# 2.net
KiCad netlist of a schematic drawn in Altium Designer
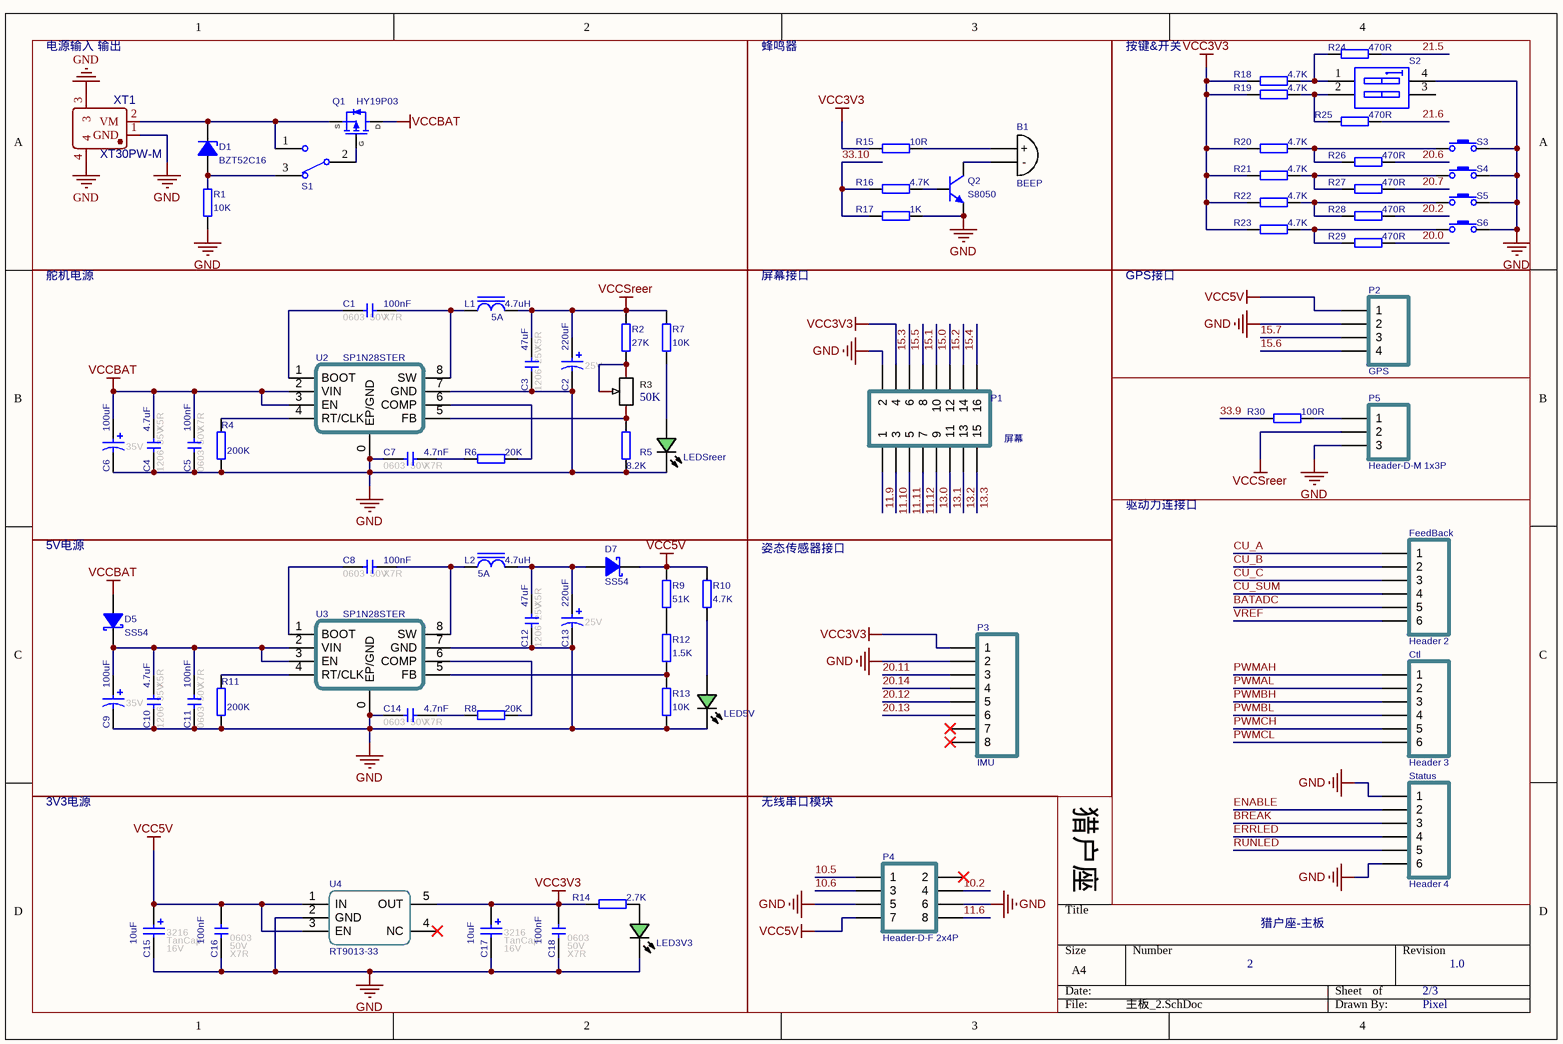
[diagram p0: 主板_2.SchDoc]

(export (version "E")
  (design (tool "Eeschema 10.0.6"))
  (components
    (comp (ref "B1")
      (value "BEEP")
      (footprint "BEEP 9x5.5mm")
      (description "蜂鸣器")
      (libsource (lib "TC264_主板_V2.6") (part "BEEP"))
    )
    (comp (ref "C1")
      (value "100nF")
      (footprint "0603")
      (description "贴片瓷片电容; MLCC; 0603(1608);")
      (fields
        (field (name "VOLTAGE") "50V")
        (field (name "TYPE") "X7R")
        (field (name "Comment") "100nF 50V X7R")
      )
      (libsource (lib "TC264_主板_V2.6") (part "100nF 0603 50V X7R"))
    )
    (comp (ref "C2")
      (value "220uF")
      (footprint "CAP-E-S 6.3")
      (description "贴片电解电容 220uF 25V 6.3x7.7")
      (fields (field (name "VOLTAGE") "25V") (field (name "Comment") "220uF 25V 铝电解"))
      (libsource (lib "TC264_主板_V2.6") (part "E-S 220uF 25V 6.3x7.7"))
    )
    (comp (ref "C3")
      (value "47uF")
      (footprint "1206")
      (description "贴片瓷片电容; MLCC; 1206(3216);")
      (fields
        (field (name "VOLTAGE") "25V")
        (field (name "TYPE") "X5R")
        (field (name "Comment") "47uF 25V X5R")
      )
      (libsource (lib "TC264_主板_V2.6") (part "47uF 1206 25V X5R"))
    )
    (comp (ref "C4")
      (value "4.7uF")
      (footprint "1206")
      (description "贴片瓷片电容; MLCC; 1206(3216);")
      (fields
        (field (name "VOLTAGE") "35V")
        (field (name "TYPE") "X5R")
        (field (name "Comment") "4.7uF 35V X5R")
      )
      (libsource (lib "TC264_主板_V2.6") (part "4.7uF 1206 35V X5R"))
    )
    (comp (ref "C5")
      (value "100nF")
      (footprint "0603")
      (description "贴片瓷片电容; MLCC; 0603(1608);")
      (fields
        (field (name "VOLTAGE") "50V")
        (field (name "TYPE") "X7R")
        (field (name "Comment") "100nF 50V X7R")
      )
      (libsource (lib "TC264_主板_V2.6") (part "100nF 0603 50V X7R"))
    )
    (comp (ref "C6")
      (value "100uF")
      (footprint "CAP-E-S 6.3")
      (description "贴片电解电容 100uF 35V 6.3x7.7")
      (fields (field (name "VOLTAGE") "35V") (field (name "Comment") "100uF 35V 铝电解"))
      (libsource (lib "TC264_主板_V2.6") (part "E-S 100uF 35V 6.3x7.7"))
    )
    (comp (ref "C7")
      (value "4.7nF")
      (footprint "0603")
      (description "贴片瓷片电容; MLCC; 0603(1608);")
      (fields
        (field (name "VOLTAGE") "50V")
        (field (name "TYPE") "X7R")
        (field (name "Comment") "4.7nF 50V X7R")
      )
      (libsource (lib "TC264_主板_V2.6") (part "4.7nF 0603 50V X7R"))
    )
    (comp (ref "C8")
      (value "100nF")
      (footprint "0603")
      (description "贴片瓷片电容; MLCC; 0603(1608);")
      (fields
        (field (name "VOLTAGE") "50V")
        (field (name "TYPE") "X7R")
        (field (name "Comment") "100nF 50V X7R")
      )
      (libsource (lib "TC264_主板_V2.6") (part "100nF 0603 50V X7R"))
    )
    (comp (ref "C9")
      (value "100uF")
      (footprint "CAP-E-S 6.3")
      (description "贴片电解电容 100uF 35V 6.3x7.7")
      (fields (field (name "VOLTAGE") "35V") (field (name "Comment") "100uF 35V 铝电解"))
      (libsource (lib "TC264_主板_V2.6") (part "E-S 100uF 35V 6.3x7.7"))
    )
    (comp (ref "C10")
      (value "4.7uF")
      (footprint "1206")
      (description "贴片瓷片电容; MLCC; 1206(3216);")
      (fields
        (field (name "VOLTAGE") "35V")
        (field (name "TYPE") "X5R")
        (field (name "Comment") "4.7uF 35V X5R")
      )
      (libsource (lib "TC264_主板_V2.6") (part "4.7uF 1206 35V X5R"))
    )
    (comp (ref "C11")
      (value "100nF")
      (footprint "0603")
      (description "贴片瓷片电容; MLCC; 0603(1608);")
      (fields
        (field (name "VOLTAGE") "50V")
        (field (name "TYPE") "X7R")
        (field (name "Comment") "100nF 50V X7R")
      )
      (libsource (lib "TC264_主板_V2.6") (part "100nF 0603 50V X7R"))
    )
    (comp (ref "C12")
      (value "47uF")
      (footprint "1206")
      (description "贴片瓷片电容; MLCC; 1206(3216);")
      (fields
        (field (name "VOLTAGE") "25V")
        (field (name "TYPE") "X5R")
        (field (name "Comment") "47uF 25V X5R")
      )
      (libsource (lib "TC264_主板_V2.6") (part "47uF 1206 25V X5R"))
    )
    (comp (ref "C13")
      (value "220uF")
      (footprint "CAP-E-S 6.3")
      (description "贴片电解电容 220uF 25V 6.3x7.7")
      (fields (field (name "VOLTAGE") "25V") (field (name "Comment") "220uF 25V 铝电解"))
      (libsource (lib "TC264_主板_V2.6") (part "E-S 220uF 25V 6.3x7.7"))
    )
    (comp (ref "C14")
      (value "4.7nF")
      (footprint "0603")
      (description "贴片瓷片电容; MLCC; 0603(1608);")
      (fields
        (field (name "VOLTAGE") "50V")
        (field (name "TYPE") "X7R")
        (field (name "Comment") "4.7nF 50V X7R")
      )
      (libsource (lib "TC264_主板_V2.6") (part "4.7nF 0603 50V X7R"))
    )
    (comp (ref "C15")
      (value "10uF")
      (footprint "3216")
      (description "贴片钽电容 10uF 3216 16V")
      (fields
        (field (name "TYPE") "TanCap")
        (field (name "VOLTAGE") "16V")
        (field (name "Comment") "10uF 16V 钽电容")
      )
      (libsource (lib "TC264_主板_V2.6") (part "T-S 10uF 3216 16V"))
    )
    (comp (ref "C16")
      (value "100nF")
      (footprint "0603")
      (description "贴片瓷片电容; MLCC; 0603(1608);")
      (fields
        (field (name "VOLTAGE") "50V")
        (field (name "TYPE") "X7R")
        (field (name "Comment") "100nF 50V X7R")
      )
      (libsource (lib "TC264_主板_V2.6") (part "100nF 0603 50V X7R"))
    )
    (comp (ref "C17")
      (value "10uF")
      (footprint "3216")
      (description "贴片钽电容 10uF 3216 16V")
      (fields
        (field (name "TYPE") "TanCap")
        (field (name "VOLTAGE") "16V")
        (field (name "Comment") "10uF 16V 钽电容")
      )
      (libsource (lib "TC264_主板_V2.6") (part "T-S 10uF 3216 16V"))
    )
    (comp (ref "C18")
      (value "100nF")
      (footprint "0603")
      (description "贴片瓷片电容; MLCC; 0603(1608);")
      (fields
        (field (name "VOLTAGE") "50V")
        (field (name "TYPE") "X7R")
        (field (name "Comment") "100nF 50V X7R")
      )
      (libsource (lib "TC264_主板_V2.6") (part "100nF 0603 50V X7R"))
    )
    (comp (ref "Ctl")
      (value "Header 3")
      (footprint "ZH1.5-6P-SH")
      (description "Header, 6-Pin")
      (fields (field (name "PUBLISHER") "Altium Limited"))
      (libsource (lib "无刷驱动-Infineon-AUIRS2181S-GTM-6S") (part "Header 6"))
    )
    (comp (ref "D1")
      (value "BZT52C16")
      (footprint "SOD-123-L")
      (description "稳压二极管 齐纳二极管  Zener Diode")
      (fields (field (name "PUBLISHER") "Altium Limited"))
      (libsource (lib "TC264_主板_V2.6") (part "Diode Zen"))
    )
    (comp (ref "D5")
      (value "SS54")
      (footprint "SMA-L[DO-214AC]")
      (description "SS54 肖特基二极管")
      (libsource (lib "TC264_主板_V2.6") (part "SS54"))
    )
    (comp (ref "D7")
      (value "SS54")
      (footprint "SMA-L[DO-214AC]")
      (description "SS54 肖特基二极管")
      (libsource (lib "TC264_主板_V2.6") (part "SS54"))
    )
    (comp (ref "FeedBack")
      (value "Header 2")
      (footprint "ZH1.5-6P-SH")
      (description "Header, 6-Pin")
      (fields (field (name "PUBLISHER") "Altium Limited"))
      (libsource (lib "无刷驱动-Infineon-AUIRS2181S-GTM-6S") (part "Header 6"))
    )
    (comp (ref "L1")
      (value "4.7uH")
      (footprint "0630 TPC 7*7*3")
      (description "功率电感")
      (fields
        (field (name "IMAX") "5A")
        (field (name "Comment") "4.7uH 5A")
        (field (name "PUBLISHER") "Altium Limited")
      )
      (libsource (lib "TC264_主板_V2.6") (part "Ind-Power"))
    )
    (comp (ref "L2")
      (value "4.7uH")
      (footprint "0630 TPC 7*7*3")
      (description "功率电感")
      (fields
        (field (name "IMAX") "5A")
        (field (name "Comment") "4.7uH 5A")
        (field (name "PUBLISHER") "Altium Limited")
      )
      (libsource (lib "TC264_主板_V2.6") (part "Ind-Power"))
    )
    (comp (ref "LED3V3")
      (value "翠绿贴片LED")
      (footprint "LEDC1608(0603)-L")
      (fields (field (name "PUBLISHER") "Altium Limited"))
      (libsource (lib "TC264_主板_V2.6") (part "LED Chip Green"))
    )
    (comp (ref "LED5V")
      (value "翠绿贴片LED")
      (footprint "LEDC1608(0603)-L")
      (fields (field (name "PUBLISHER") "Altium Limited"))
      (libsource (lib "TC264_主板_V2.6") (part "LED Chip Green"))
    )
    (comp (ref "LEDSreer")
      (value "翠绿贴片LED")
      (footprint "LEDC1608(0603)-L")
      (fields (field (name "PUBLISHER") "Altium Limited"))
      (libsource (lib "TC264_主板_V2.6") (part "LED Chip Green"))
    )
    (comp (ref "P1")
      (value "屏幕")
      (footprint "HDR2X8-F")
      (description "2x8pin, 直插, 双排座")
      (libsource (lib "TC264_主板_V2.6") (part "Header-D-F 2x8P"))
    )
    (comp (ref "P2")
      (value "GPS")
      (footprint "HDR1X4-M")
      (description "1x4pin, 直插, 排针")
      (libsource (lib "TC264_主板_V2.6") (part "Header-D-M 1x4P"))
    )
    (comp (ref "P3")
      (value "IMU")
      (footprint "HDR1X8-M")
      (description "1x8pin, 直插, 排针")
      (libsource (lib "TC264_主板_V2.6") (part "Header-D-M 1x8P"))
    )
    (comp (ref "P4")
      (value "Header-D-F 2x4P")
      (footprint "HDR2X4-F")
      (description "2x4pin, 直插, 双排座")
      (libsource (lib "TC264_主板_V2.6") (part "Header-D-F 2x4P"))
    )
    (comp (ref "P5")
      (value "Header-D-M 1x3P")
      (footprint "HDR1X3-M")
      (description "1x3pin, 直插, 排针")
      (libsource (lib "TC264_主板_V2.6") (part "Header-D-M 1x3P"))
    )
    (comp (ref "Q1")
      (value "HY19P03")
      (footprint "TO-252AA")
      (description "HY19P03 P-Channel MOSFET")
      (libsource (lib "TC264_主板_V2.6") (part "HY19P03"))
    )
    (comp (ref "Q2")
      (value "S8050")
      (footprint "SOT-23")
      (description "NPN 三极管")
      (fields (field (name "PARTNUMBER") "S8050") (field (name "PUBLISHER") "Altium Limited"))
      (libsource (lib "TC264_主板_V2.6") (part "NPN S8050"))
    )
    (comp (ref "R1")
      (value "10K")
      (footprint "RESC1608[0603]S-N")
      (description "贴片电阻")
      (fields (field (name "POWER") "1/8W") (field (name "TOLERANCE") "±1%"))
      (libsource (lib "TC264_主板_V2.6") (part "Res-Chip"))
    )
    (comp (ref "R2")
      (value "27K")
      (footprint "RESC1608[0603]S-N")
      (description "贴片电阻")
      (fields (field (name "POWER") "1/8W") (field (name "TOLERANCE") "±1%"))
      (libsource (lib "TC264_主板_V2.6") (part "Res-Chip_7"))
    )
    (comp (ref "R3")
      (value "3362P-1-503")
      (footprint "RES-ADJ-TH_3P-L7.1-W6.9-P2.50-L_3362P")
      (fields (field (name "DESIGNER") "U?"))
      (libsource (lib "RES-ADJ-50K(10%)") (part "RES-ADJ-50k(10%)"))
    )
    (comp (ref "R4")
      (value "200K")
      (footprint "RESC1608[0603]S-N")
      (description "贴片电阻")
      (fields (field (name "POWER") "1/8W") (field (name "TOLERANCE") "±1%"))
      (libsource (lib "TC264_主板_V2.6") (part "Res-Chip_1"))
    )
    (comp (ref "R5")
      (value "8.2K")
      (footprint "RESC1608[0603]S-N")
      (description "贴片电阻")
      (fields (field (name "POWER") "1/8W") (field (name "TOLERANCE") "±1%"))
      (libsource (lib "TC264_主板_V2.6") (part "Res-Chip_8"))
    )
    (comp (ref "R6")
      (value "20K")
      (footprint "RESC1608[0603]S-N")
      (description "贴片电阻")
      (fields (field (name "POWER") "1/8W") (field (name "TOLERANCE") "±1%"))
      (libsource (lib "TC264_主板_V2.6") (part "Res-Chip_4"))
    )
    (comp (ref "R7")
      (value "10K")
      (footprint "RESC1608[0603]S-N")
      (description "贴片电阻")
      (fields (field (name "POWER") "1/8W") (field (name "TOLERANCE") "±1%"))
      (libsource (lib "TC264_主板_V2.6") (part "Res-Chip"))
    )
    (comp (ref "R8")
      (value "20K")
      (footprint "RESC1608[0603]S-N")
      (description "贴片电阻")
      (fields (field (name "POWER") "1/8W") (field (name "TOLERANCE") "±1%"))
      (libsource (lib "TC264_主板_V2.6") (part "Res-Chip_4"))
    )
    (comp (ref "R9")
      (value "51K")
      (footprint "RESC1608[0603]S-N")
      (description "贴片电阻")
      (fields (field (name "POWER") "1/8W") (field (name "TOLERANCE") "±1%"))
      (libsource (lib "TC264_主板_V2.6") (part "Res-Chip_7"))
    )
    (comp (ref "R10")
      (value "4.7K")
      (footprint "RESC1608[0603]S-N")
      (description "贴片电阻")
      (fields (field (name "POWER") "1/8W") (field (name "TOLERANCE") "±1%"))
      (libsource (lib "TC264_主板_V2.6") (part "Res-Chip_3"))
    )
    (comp (ref "R11")
      (value "200K")
      (footprint "RESC1608[0603]S-N")
      (description "贴片电阻")
      (fields (field (name "POWER") "1/8W") (field (name "TOLERANCE") "±1%"))
      (libsource (lib "TC264_主板_V2.6") (part "Res-Chip_1"))
    )
    (comp (ref "R12")
      (value "1.5K")
      (footprint "RESC1608[0603]S-N")
      (description "贴片电阻")
      (fields (field (name "POWER") "1/8W") (field (name "TOLERANCE") "±1%"))
      (libsource (lib "TC264_主板_V2.6") (part "Res-Chip_5"))
    )
    (comp (ref "R13")
      (value "10K")
      (footprint "RESC1608[0603]S-N")
      (description "贴片电阻")
      (fields (field (name "POWER") "1/8W") (field (name "TOLERANCE") "±1%"))
      (libsource (lib "TC264_主板_V2.6") (part "Res-Chip"))
    )
    (comp (ref "R14")
      (value "2.7K")
      (footprint "RESC1608[0603]S-N")
      (description "贴片电阻")
      (fields (field (name "POWER") "1/8W") (field (name "TOLERANCE") "±1%"))
      (libsource (lib "TC264_主板_V2.6") (part "Res-Chip_6"))
    )
    (comp (ref "R15")
      (value "10R")
      (footprint "RESC1608[0603]S-N")
      (description "贴片电阻")
      (fields (field (name "POWER") "1/8W") (field (name "TOLERANCE") "±1%"))
      (libsource (lib "TC264_主板_V2.6") (part "Res-Chip_10"))
    )
    (comp (ref "R16")
      (value "4.7K")
      (footprint "RESC1608[0603]S-N")
      (description "贴片电阻")
      (fields (field (name "POWER") "1/8W") (field (name "TOLERANCE") "±1%"))
      (libsource (lib "TC264_主板_V2.6") (part "Res-Chip_3"))
    )
    (comp (ref "R17")
      (value "1K")
      (footprint "RESC1608[0603]S-N")
      (description "贴片电阻")
      (fields (field (name "POWER") "1/8W") (field (name "TOLERANCE") "±1%"))
      (libsource (lib "TC264_主板_V2.6") (part "Res-Chip_11"))
    )
    (comp (ref "R18")
      (value "4.7K")
      (footprint "RESC1608[0603]S-N")
      (description "贴片电阻")
      (fields (field (name "POWER") "1/8W") (field (name "TOLERANCE") "±1%"))
      (libsource (lib "TC264_主板_V2.6") (part "Res-Chip_3"))
    )
    (comp (ref "R19")
      (value "4.7K")
      (footprint "RESC1608[0603]S-N")
      (description "贴片电阻")
      (fields (field (name "POWER") "1/8W") (field (name "TOLERANCE") "±1%"))
      (libsource (lib "TC264_主板_V2.6") (part "Res-Chip_3"))
    )
    (comp (ref "R20")
      (value "4.7K")
      (footprint "RESC1608[0603]S-N")
      (description "贴片电阻")
      (fields (field (name "POWER") "1/8W") (field (name "TOLERANCE") "±1%"))
      (libsource (lib "TC264_主板_V2.6") (part "Res-Chip_3"))
    )
    (comp (ref "R21")
      (value "4.7K")
      (footprint "RESC1608[0603]S-N")
      (description "贴片电阻")
      (fields (field (name "POWER") "1/8W") (field (name "TOLERANCE") "±1%"))
      (libsource (lib "TC264_主板_V2.6") (part "Res-Chip_3"))
    )
    (comp (ref "R22")
      (value "4.7K")
      (footprint "RESC1608[0603]S-N")
      (description "贴片电阻")
      (fields (field (name "POWER") "1/8W") (field (name "TOLERANCE") "±1%"))
      (libsource (lib "TC264_主板_V2.6") (part "Res-Chip_3"))
    )
    (comp (ref "R23")
      (value "4.7K")
      (footprint "RESC1608[0603]S-N")
      (description "贴片电阻")
      (fields (field (name "POWER") "1/8W") (field (name "TOLERANCE") "±1%"))
      (libsource (lib "TC264_主板_V2.6") (part "Res-Chip_3"))
    )
    (comp (ref "R24")
      (value "470R")
      (footprint "RESC1608[0603]S-N")
      (description "贴片电阻")
      (fields (field (name "POWER") "1/8W") (field (name "TOLERANCE") "±1%"))
      (libsource (lib "TC264_主板_V2.6") (part "Res-Chip_12"))
    )
    (comp (ref "R25")
      (value "470R")
      (footprint "RESC1608[0603]S-N")
      (description "贴片电阻")
      (fields (field (name "POWER") "1/8W") (field (name "TOLERANCE") "±1%"))
      (libsource (lib "TC264_主板_V2.6") (part "Res-Chip_12"))
    )
    (comp (ref "R26")
      (value "470R")
      (footprint "RESC1608[0603]S-N")
      (description "贴片电阻")
      (fields (field (name "POWER") "1/8W") (field (name "TOLERANCE") "±1%"))
      (libsource (lib "TC264_主板_V2.6") (part "Res-Chip_12"))
    )
    (comp (ref "R27")
      (value "470R")
      (footprint "RESC1608[0603]S-N")
      (description "贴片电阻")
      (fields (field (name "POWER") "1/8W") (field (name "TOLERANCE") "±1%"))
      (libsource (lib "TC264_主板_V2.6") (part "Res-Chip_12"))
    )
    (comp (ref "R28")
      (value "470R")
      (footprint "RESC1608[0603]S-N")
      (description "贴片电阻")
      (fields (field (name "POWER") "1/8W") (field (name "TOLERANCE") "±1%"))
      (libsource (lib "TC264_主板_V2.6") (part "Res-Chip_12"))
    )
    (comp (ref "R29")
      (value "470R")
      (footprint "RESC1608[0603]S-N")
      (description "贴片电阻")
      (fields (field (name "POWER") "1/8W") (field (name "TOLERANCE") "±1%"))
      (libsource (lib "TC264_主板_V2.6") (part "Res-Chip_12"))
    )
    (comp (ref "R30")
      (value "100R")
      (footprint "RESC1608[0603]S-N")
      (description "贴片电阻")
      (fields (field (name "POWER") "1/8W") (field (name "TOLERANCE") "±1%"))
      (libsource (lib "TC264_主板_V2.6") (part "Res-Chip_9"))
    )
    (comp (ref "S1")
      (value "SW-SPDT")
      (footprint "SS12D10")
      (description "单刀双掷开关 3脚船型、钮子、拨动开关 SPDT Subminiature Toggle Switch")
      (fields (field (name "PUBLISHER") "Altium Limited"))
      (libsource (lib "TC264_主板_V2.6") (part "SW-SPDT"))
    )
    (comp (ref "S2")
      (value "SW DIP-2")
      (footprint "Code SW-2-DIP-2.54")
      (description "2位拨码开关")
      (fields (field (name "PUBLISHER") "Altium Limited"))
      (libsource (lib "TC264_主板_V2.6") (part "Code SW-2"))
    )
    (comp (ref "S3")
      (value "Button")
      (footprint "PTS810-3*4-CurvePin")
      (description "按键")
      (fields (field (name "PUBLISHER") "Altium Limited"))
      (libsource (lib "TC264_主板_V2.6") (part "KEY"))
    )
    (comp (ref "S4")
      (value "Button")
      (footprint "PTS810-3*4-CurvePin")
      (description "按键")
      (fields (field (name "PUBLISHER") "Altium Limited"))
      (libsource (lib "TC264_主板_V2.6") (part "KEY"))
    )
    (comp (ref "S5")
      (value "Button")
      (footprint "PTS810-3*4-CurvePin")
      (description "按键")
      (fields (field (name "PUBLISHER") "Altium Limited"))
      (libsource (lib "TC264_主板_V2.6") (part "KEY"))
    )
    (comp (ref "S6")
      (value "Button")
      (footprint "PTS810-3*4-CurvePin")
      (description "按键")
      (fields (field (name "PUBLISHER") "Altium Limited"))
      (libsource (lib "TC264_主板_V2.6") (part "KEY"))
    )
    (comp (ref "Status")
      (value "Header 4")
      (footprint "ZH1.5-6P-SH")
      (description "Header, 6-Pin")
      (fields (field (name "PUBLISHER") "Altium Limited"))
      (libsource (lib "无刷驱动-Infineon-AUIRS2181S-GTM-6S") (part "Header 6"))
    )
    (comp (ref "U2")
      (value "SP1N28STER")
      (footprint "SOP-8E")
      (libsource (lib "TC264_主板_V2.6") (part "SP1N28STER"))
    )
    (comp (ref "U3")
      (value "SP1N28STER")
      (footprint "SOP-8E")
      (libsource (lib "TC264_主板_V2.6") (part "SP1N28STER"))
    )
    (comp (ref "U4")
      (value "RT9013-33")
      (footprint "SOT-23-5")
      (description "3.3V 500mA SOT-23-5 LDO")
      (libsource (lib "TC264_主板_V2.6") (part "RT9013-33"))
    )
    (comp (ref "XT1") (value "XT30PW-M") (footprint "XT30PW-M") (libsource (lib "XT30-M") (part "XT30PW-M")))
  )
  (nets
    (net (code "1") (name "/10.2") (class "Default")
      (node (ref "P4") (pin "4") (pinfunction "4_4") (pintype "passive"))
    )
    (net (code "2") (name "/10.5") (class "Default")
      (node (ref "P4") (pin "1") (pinfunction "1_1") (pintype "passive"))
    )
    (net (code "3") (name "/10.6") (class "Default")
      (node (ref "P4") (pin "3") (pinfunction "3_3") (pintype "passive"))
    )
    (net (code "4") (name "/11.6") (class "Default")
      (node (ref "P4") (pin "8") (pinfunction "8_8") (pintype "passive"))
    )
    (net (code "5") (name "/11.9") (class "Default")
      (node (ref "P1") (pin "1") (pinfunction "1_1") (pintype "passive"))
    )
    (net (code "6") (name "/11.10") (class "Default")
      (node (ref "P1") (pin "3") (pinfunction "3_3") (pintype "passive"))
    )
    (net (code "7") (name "/11.11") (class "Default")
      (node (ref "P1") (pin "5") (pinfunction "5_5") (pintype "passive"))
    )
    (net (code "8") (name "/11.12") (class "Default")
      (node (ref "P1") (pin "7") (pinfunction "7_7") (pintype "passive"))
    )
    (net (code "9") (name "/13.0") (class "Default")
      (node (ref "P1") (pin "9") (pinfunction "9_9") (pintype "passive"))
    )
    (net (code "10") (name "/13.1") (class "Default")
      (node (ref "P1") (pin "11") (pinfunction "11_11") (pintype "passive"))
    )
    (net (code "11") (name "/13.2") (class "Default")
      (node (ref "P1") (pin "13") (pinfunction "13_13") (pintype "passive"))
    )
    (net (code "12") (name "/13.3") (class "Default")
      (node (ref "P1") (pin "15") (pinfunction "15_15") (pintype "passive"))
    )
    (net (code "13") (name "/15.0") (class "Default")
      (node (ref "P1") (pin "12") (pinfunction "12_12") (pintype "passive"))
    )
    (net (code "14") (name "/15.1") (class "Default")
      (node (ref "P1") (pin "10") (pinfunction "10_10") (pintype "passive"))
    )
    (net (code "15") (name "/15.2") (class "Default")
      (node (ref "P1") (pin "14") (pinfunction "14_14") (pintype "passive"))
    )
    (net (code "16") (name "/15.3") (class "Default")
      (node (ref "P1") (pin "6") (pinfunction "6_6") (pintype "passive"))
    )
    (net (code "17") (name "/15.4") (class "Default")
      (node (ref "P1") (pin "16") (pinfunction "16_16") (pintype "passive"))
    )
    (net (code "18") (name "/15.5") (class "Default")
      (node (ref "P1") (pin "8") (pinfunction "8_8") (pintype "passive"))
    )
    (net (code "19") (name "/15.6") (class "Default")
      (node (ref "P2") (pin "4") (pinfunction "4_4") (pintype "passive"))
    )
    (net (code "20") (name "/15.7") (class "Default")
      (node (ref "P2") (pin "3") (pinfunction "3_3") (pintype "passive"))
    )
    (net (code "21") (name "/20.0") (class "Default")
      (node (ref "R29") (pin "2") (pinfunction "2_2") (pintype "passive"))
    )
    (net (code "22") (name "/20.2") (class "Default")
      (node (ref "R28") (pin "2") (pinfunction "2_2") (pintype "passive"))
    )
    (net (code "23") (name "/20.6") (class "Default")
      (node (ref "R26") (pin "2") (pinfunction "2_2") (pintype "passive"))
    )
    (net (code "24") (name "/20.7") (class "Default")
      (node (ref "R27") (pin "2") (pinfunction "2_2") (pintype "passive"))
    )
    (net (code "25") (name "/20.11") (class "Default")
      (node (ref "P3") (pin "3") (pinfunction "3_3") (pintype "passive"))
    )
    (net (code "26") (name "/20.12") (class "Default")
      (node (ref "P3") (pin "5") (pinfunction "5_5") (pintype "passive"))
    )
    (net (code "27") (name "/20.13") (class "Default")
      (node (ref "P3") (pin "6") (pinfunction "6_6") (pintype "passive"))
    )
    (net (code "28") (name "/20.14") (class "Default")
      (node (ref "P3") (pin "4") (pinfunction "4_4") (pintype "passive"))
    )
    (net (code "29") (name "/21.5") (class "Default")
      (node (ref "R24") (pin "2") (pinfunction "2_2") (pintype "passive"))
    )
    (net (code "30") (name "/21.6") (class "Default")
      (node (ref "R25") (pin "2") (pinfunction "2_2") (pintype "passive"))
    )
    (net (code "31") (name "/33.9") (class "Default")
      (node (ref "R30") (pin "1") (pinfunction "1_1") (pintype "passive"))
    )
    (net (code "32") (name "/33.10") (class "Default")
      (node (ref "R16") (pin "1") (pinfunction "1_1") (pintype "passive"))
      (node (ref "R17") (pin "1") (pinfunction "1_1") (pintype "passive"))
    )
    (net (code "33") (name "/BATADC") (class "Default")
      (node (ref "FeedBack") (pin "5") (pinfunction "5_5") (pintype "passive"))
    )
    (net (code "34") (name "/BREAK") (class "Default")
      (node (ref "Status") (pin "3") (pinfunction "3_3") (pintype "passive"))
    )
    (net (code "35") (name "/CU_A") (class "Default")
      (node (ref "FeedBack") (pin "1") (pinfunction "1_1") (pintype "passive"))
    )
    (net (code "36") (name "/CU_B") (class "Default")
      (node (ref "FeedBack") (pin "2") (pinfunction "2_2") (pintype "passive"))
    )
    (net (code "37") (name "/CU_C") (class "Default")
      (node (ref "FeedBack") (pin "3") (pinfunction "3_3") (pintype "passive"))
    )
    (net (code "38") (name "/CU_SUM") (class "Default")
      (node (ref "FeedBack") (pin "4") (pinfunction "4_4") (pintype "passive"))
    )
    (net (code "39") (name "/ENABLE") (class "Default")
      (node (ref "Status") (pin "2") (pinfunction "2_2") (pintype "passive"))
    )
    (net (code "40") (name "/ERRLED") (class "Default")
      (node (ref "Status") (pin "4") (pinfunction "4_4") (pintype "passive"))
    )
    (net (code "41") (name "/PWMAH") (class "Default")
      (node (ref "Ctl") (pin "1") (pinfunction "1_1") (pintype "passive"))
    )
    (net (code "42") (name "/PWMAL") (class "Default")
      (node (ref "Ctl") (pin "2") (pinfunction "2_2") (pintype "passive"))
    )
    (net (code "43") (name "/PWMBH") (class "Default")
      (node (ref "Ctl") (pin "3") (pinfunction "3_3") (pintype "passive"))
    )
    (net (code "44") (name "/PWMBL") (class "Default")
      (node (ref "Ctl") (pin "4") (pinfunction "4_4") (pintype "passive"))
    )
    (net (code "45") (name "/PWMCH") (class "Default")
      (node (ref "Ctl") (pin "5") (pinfunction "5_5") (pintype "passive"))
    )
    (net (code "46") (name "/PWMCL") (class "Default")
      (node (ref "Ctl") (pin "6") (pinfunction "6_6") (pintype "passive"))
    )
    (net (code "47") (name "/RUNLED") (class "Default")
      (node (ref "Status") (pin "5") (pinfunction "5_5") (pintype "passive"))
    )
    (net (code "48") (name "/VREF") (class "Default")
      (node (ref "FeedBack") (pin "6") (pinfunction "6_6") (pintype "passive"))
    )
    (net (code "49") (name "GND") (class "Default")
      (node (ref "C10") (pin "1") (pinfunction "1_1") (pintype "passive"))
      (node (ref "C11") (pin "1") (pinfunction "1_1") (pintype "passive"))
      (node (ref "C12") (pin "1") (pinfunction "1_1") (pintype "passive"))
      (node (ref "C13") (pin "2") (pinfunction "2_2") (pintype "passive"))
      (node (ref "C14") (pin "1") (pinfunction "1_1") (pintype "passive"))
      (node (ref "C15") (pin "2") (pinfunction "2_2") (pintype "passive"))
      (node (ref "C16") (pin "1") (pinfunction "1_1") (pintype "passive"))
      (node (ref "C17") (pin "2") (pinfunction "2_2") (pintype "passive"))
      (node (ref "C18") (pin "1") (pinfunction "1_1") (pintype "passive"))
      (node (ref "C2") (pin "2") (pinfunction "2_2") (pintype "passive"))
      (node (ref "C3") (pin "1") (pinfunction "1_1") (pintype "passive"))
      (node (ref "C4") (pin "1") (pinfunction "1_1") (pintype "passive"))
      (node (ref "C5") (pin "1") (pinfunction "1_1") (pintype "passive"))
      (node (ref "C6") (pin "2") (pinfunction "2_2") (pintype "passive"))
      (node (ref "C7") (pin "1") (pinfunction "1_1") (pintype "passive"))
      (node (ref "C9") (pin "2") (pinfunction "2_2") (pintype "passive"))
      (node (ref "LED3V3") (pin "C") (pinfunction "C_C") (pintype "passive"))
      (node (ref "LED5V") (pin "C") (pinfunction "C_C") (pintype "passive"))
      (node (ref "LEDSreer") (pin "C") (pinfunction "C_C") (pintype "passive"))
      (node (ref "P1") (pin "2") (pinfunction "2_2") (pintype "passive"))
      (node (ref "P2") (pin "2") (pinfunction "2_2") (pintype "passive"))
      (node (ref "P3") (pin "2") (pinfunction "2_2") (pintype "passive"))
      (node (ref "P4") (pin "5") (pinfunction "5_5") (pintype "passive"))
      (node (ref "P4") (pin "6") (pinfunction "6_6") (pintype "passive"))
      (node (ref "P5") (pin "3") (pinfunction "3_3") (pintype "passive"))
      (node (ref "Q2") (pin "2") (pinfunction "E_2") (pintype "passive"))
      (node (ref "R1") (pin "1") (pinfunction "1_1") (pintype "passive"))
      (node (ref "R11") (pin "1") (pinfunction "1_1") (pintype "passive"))
      (node (ref "R13") (pin "1") (pinfunction "1_1") (pintype "passive"))
      (node (ref "R17") (pin "2") (pinfunction "2_2") (pintype "passive"))
      (node (ref "R4") (pin "1") (pinfunction "1_1") (pintype "passive"))
      (node (ref "R5") (pin "1") (pinfunction "1_1") (pintype "passive"))
      (node (ref "S2") (pin "4") (pinfunction "B1_4") (pintype "passive"))
      (node (ref "S3") (pin "1") (pinfunction "1_1") (pintype "passive"))
      (node (ref "S4") (pin "1") (pinfunction "1_1") (pintype "passive"))
      (node (ref "S5") (pin "1") (pinfunction "1_1") (pintype "passive"))
      (node (ref "S6") (pin "1") (pinfunction "1_1") (pintype "passive"))
      (node (ref "Status") (pin "1") (pinfunction "1_1") (pintype "passive"))
      (node (ref "Status") (pin "6") (pinfunction "6_6") (pintype "passive"))
      (node (ref "U2") (pin "0") (pinfunction "EP/GND_0") (pintype "passive"))
      (node (ref "U2") (pin "7") (pinfunction "GND_7") (pintype "passive"))
      (node (ref "U3") (pin "0") (pinfunction "EP/GND_0") (pintype "passive"))
      (node (ref "U3") (pin "7") (pinfunction "GND_7") (pintype "passive"))
      (node (ref "U4") (pin "2") (pinfunction "GND_2") (pintype "passive"))
      (node (ref "XT1") (pin "1") (pinfunction "GND_1") (pintype "passive"))
      (node (ref "XT1") (pin "3") (pinfunction "3_3") (pintype "passive"))
      (node (ref "XT1") (pin "4") (pinfunction "4_4") (pintype "passive"))
    )
    (net (code "50") (name "Net-(B1-+)") (class "Default")
      (node (ref "B1") (pin "1") (pinfunction "+_1") (pintype "passive"))
      (node (ref "R15") (pin "2") (pinfunction "2_2") (pintype "passive"))
    )
    (net (code "51") (name "Net-(B1--)") (class "Default")
      (node (ref "B1") (pin "2") (pinfunction "-_2") (pintype "passive"))
      (node (ref "Q2") (pin "3") (pinfunction "C_3") (pintype "passive"))
    )
    (net (code "52") (name "Net-(C7-Pad2)") (class "Default")
      (node (ref "C7") (pin "2") (pinfunction "2_2") (pintype "passive"))
      (node (ref "R6") (pin "1") (pinfunction "1_1") (pintype "passive"))
    )
    (net (code "53") (name "Net-(C12-Pad2)") (class "Default")
      (node (ref "C12") (pin "2") (pinfunction "2_2") (pintype "passive"))
      (node (ref "C13") (pin "1") (pinfunction "1_1") (pintype "passive"))
      (node (ref "D7") (pin "A") (pinfunction "A_A") (pintype "passive"))
      (node (ref "L2") (pin "2") (pinfunction "2_2") (pintype "passive"))
    )
    (net (code "54") (name "Net-(C14-Pad2)") (class "Default")
      (node (ref "C14") (pin "2") (pinfunction "2_2") (pintype "passive"))
      (node (ref "R8") (pin "1") (pinfunction "1_1") (pintype "passive"))
    )
    (net (code "55") (name "Net-(D1-PadA)") (class "Default")
      (node (ref "D1") (pin "A") (pinfunction "A_A") (pintype "passive"))
      (node (ref "R1") (pin "2") (pinfunction "2_2") (pintype "passive"))
      (node (ref "S1") (pin "3") (pintype "passive"))
    )
    (net (code "56") (name "Net-(LED3V3-PadA)") (class "Default")
      (node (ref "LED3V3") (pin "A") (pinfunction "A_A") (pintype "passive"))
      (node (ref "R14") (pin "2") (pinfunction "2_2") (pintype "passive"))
    )
    (net (code "57") (name "Net-(LED5V-PadA)") (class "Default")
      (node (ref "LED5V") (pin "A") (pinfunction "A_A") (pintype "passive"))
      (node (ref "R10") (pin "1") (pinfunction "1_1") (pintype "passive"))
    )
    (net (code "58") (name "Net-(LEDSreer-PadA)") (class "Default")
      (node (ref "LEDSreer") (pin "A") (pinfunction "A_A") (pintype "passive"))
      (node (ref "R7") (pin "1") (pinfunction "1_1") (pintype "passive"))
    )
    (net (code "59") (name "Net-(P5-Pad1)") (class "Default")
      (node (ref "P5") (pin "1") (pinfunction "1_1") (pintype "passive"))
      (node (ref "R30") (pin "2") (pinfunction "2_2") (pintype "passive"))
    )
    (net (code "60") (name "Net-(Q1-G)") (class "Default")
      (node (ref "Q1") (pin "2") (pinfunction "G_2") (pintype "passive"))
      (node (ref "S1") (pin "2") (pintype "passive"))
    )
    (net (code "61") (name "Net-(Q1-S)") (class "Default")
      (node (ref "D1") (pin "K") (pinfunction "K_K") (pintype "passive"))
      (node (ref "Q1") (pin "3") (pinfunction "S_3") (pintype "passive"))
      (node (ref "S1") (pin "1") (pintype "passive"))
      (node (ref "XT1") (pin "2") (pinfunction "VM_2") (pintype "passive"))
    )
    (net (code "62") (name "Net-(Q2-B)") (class "Default")
      (node (ref "Q2") (pin "1") (pinfunction "B_1") (pintype "passive"))
      (node (ref "R16") (pin "2") (pinfunction "2_2") (pintype "passive"))
    )
    (net (code "63") (name "Net-(R2-Pad1)") (class "Default")
      (node (ref "R2") (pin "1") (pinfunction "1_1") (pintype "passive"))
      (node (ref "R3") (pin "2") (pinfunction "2_2") (pintype "passive"))
      (node (ref "R3") (pin "3") (pinfunction "3_3") (pintype "passive"))
    )
    (net (code "64") (name "Net-(R12-Pad2)") (class "Default")
      (node (ref "R12") (pin "2") (pinfunction "2_2") (pintype "passive"))
      (node (ref "R9") (pin "1") (pinfunction "1_1") (pintype "passive"))
    )
    (net (code "65") (name "Net-(R20-Pad2)") (class "Default")
      (node (ref "R20") (pin "2") (pinfunction "2_2") (pintype "passive"))
      (node (ref "R26") (pin "1") (pinfunction "1_1") (pintype "passive"))
      (node (ref "S3") (pin "2") (pinfunction "2_2") (pintype "passive"))
    )
    (net (code "66") (name "Net-(R21-Pad2)") (class "Default")
      (node (ref "R21") (pin "2") (pinfunction "2_2") (pintype "passive"))
      (node (ref "R27") (pin "1") (pinfunction "1_1") (pintype "passive"))
      (node (ref "S4") (pin "2") (pinfunction "2_2") (pintype "passive"))
    )
    (net (code "67") (name "Net-(R22-Pad2)") (class "Default")
      (node (ref "R22") (pin "2") (pinfunction "2_2") (pintype "passive"))
      (node (ref "R28") (pin "1") (pinfunction "1_1") (pintype "passive"))
      (node (ref "S5") (pin "2") (pinfunction "2_2") (pintype "passive"))
    )
    (net (code "68") (name "Net-(R23-Pad2)") (class "Default")
      (node (ref "R23") (pin "2") (pinfunction "2_2") (pintype "passive"))
      (node (ref "R29") (pin "1") (pinfunction "1_1") (pintype "passive"))
      (node (ref "S6") (pin "2") (pinfunction "2_2") (pintype "passive"))
    )
    (net (code "69") (name "Net-(S2-A1)") (class "Default")
      (node (ref "R18") (pin "2") (pinfunction "2_2") (pintype "passive"))
      (node (ref "R24") (pin "1") (pinfunction "1_1") (pintype "passive"))
      (node (ref "S2") (pin "1") (pinfunction "A1_1") (pintype "passive"))
    )
    (net (code "70") (name "Net-(S2-A2)") (class "Default")
      (node (ref "R19") (pin "2") (pinfunction "2_2") (pintype "passive"))
      (node (ref "R25") (pin "1") (pinfunction "1_1") (pintype "passive"))
      (node (ref "S2") (pin "2") (pinfunction "A2_2") (pintype "passive"))
    )
    (net (code "71") (name "Net-(U2-BOOT)") (class "Default")
      (node (ref "C1") (pin "1") (pinfunction "1_1") (pintype "passive"))
      (node (ref "U2") (pin "1") (pinfunction "BOOT_1") (pintype "passive"))
    )
    (net (code "72") (name "Net-(U2-COMP)") (class "Default")
      (node (ref "R6") (pin "2") (pinfunction "2_2") (pintype "passive"))
      (node (ref "U2") (pin "6") (pinfunction "COMP_6") (pintype "passive"))
    )
    (net (code "73") (name "Net-(U2-FB)") (class "Default")
      (node (ref "R3") (pin "1") (pinfunction "1_1") (pintype "passive"))
      (node (ref "R5") (pin "2") (pinfunction "2_2") (pintype "passive"))
      (node (ref "U2") (pin "5") (pinfunction "FB_5") (pintype "passive"))
    )
    (net (code "74") (name "Net-(U2-RT{slash}CLK)") (class "Default")
      (node (ref "R4") (pin "2") (pinfunction "2_2") (pintype "passive"))
      (node (ref "U2") (pin "4") (pinfunction "RT/CLK_4") (pintype "passive"))
    )
    (net (code "75") (name "Net-(U2-SW)") (class "Default")
      (node (ref "C1") (pin "2") (pinfunction "2_2") (pintype "passive"))
      (node (ref "L1") (pin "1") (pinfunction "1_1") (pintype "passive"))
      (node (ref "U2") (pin "8") (pinfunction "SW_8") (pintype "passive"))
    )
    (net (code "76") (name "Net-(U3-BOOT)") (class "Default")
      (node (ref "C8") (pin "1") (pinfunction "1_1") (pintype "passive"))
      (node (ref "U3") (pin "1") (pinfunction "BOOT_1") (pintype "passive"))
    )
    (net (code "77") (name "Net-(U3-COMP)") (class "Default")
      (node (ref "R8") (pin "2") (pinfunction "2_2") (pintype "passive"))
      (node (ref "U3") (pin "6") (pinfunction "COMP_6") (pintype "passive"))
    )
    (net (code "78") (name "Net-(U3-EN)") (class "Default")
      (node (ref "C10") (pin "2") (pinfunction "2_2") (pintype "passive"))
      (node (ref "C11") (pin "2") (pinfunction "2_2") (pintype "passive"))
      (node (ref "C9") (pin "1") (pinfunction "1_1") (pintype "passive"))
      (node (ref "D5") (pin "K") (pinfunction "K_K") (pintype "passive"))
      (node (ref "U3") (pin "2") (pinfunction "VIN_2") (pintype "passive"))
      (node (ref "U3") (pin "3") (pinfunction "EN_3") (pintype "passive"))
    )
    (net (code "79") (name "Net-(U3-FB)") (class "Default")
      (node (ref "R12") (pin "1") (pinfunction "1_1") (pintype "passive"))
      (node (ref "R13") (pin "2") (pinfunction "2_2") (pintype "passive"))
      (node (ref "U3") (pin "5") (pinfunction "FB_5") (pintype "passive"))
    )
    (net (code "80") (name "Net-(U3-RT{slash}CLK)") (class "Default")
      (node (ref "R11") (pin "2") (pinfunction "2_2") (pintype "passive"))
      (node (ref "U3") (pin "4") (pinfunction "RT/CLK_4") (pintype "passive"))
    )
    (net (code "81") (name "Net-(U3-SW)") (class "Default")
      (node (ref "C8") (pin "2") (pinfunction "2_2") (pintype "passive"))
      (node (ref "L2") (pin "1") (pinfunction "1_1") (pintype "passive"))
      (node (ref "U3") (pin "8") (pinfunction "SW_8") (pintype "passive"))
    )
    (net (code "82") (name "VCC3V3") (class "Default")
      (node (ref "C17") (pin "1") (pinfunction "1_1") (pintype "passive"))
      (node (ref "C18") (pin "2") (pinfunction "2_2") (pintype "passive"))
      (node (ref "P1") (pin "4") (pinfunction "4_4") (pintype "passive"))
      (node (ref "P3") (pin "1") (pinfunction "1_1") (pintype "passive"))
      (node (ref "R14") (pin "1") (pinfunction "1_1") (pintype "passive"))
      (node (ref "R15") (pin "1") (pinfunction "1_1") (pintype "passive"))
      (node (ref "R18") (pin "1") (pinfunction "1_1") (pintype "passive"))
      (node (ref "R19") (pin "1") (pinfunction "1_1") (pintype "passive"))
      (node (ref "R20") (pin "1") (pinfunction "1_1") (pintype "passive"))
      (node (ref "R21") (pin "1") (pinfunction "1_1") (pintype "passive"))
      (node (ref "R22") (pin "1") (pinfunction "1_1") (pintype "passive"))
      (node (ref "R23") (pin "1") (pinfunction "1_1") (pintype "passive"))
      (node (ref "U4") (pin "5") (pinfunction "OUT_5") (pintype "passive"))
    )
    (net (code "83") (name "VCC5V") (class "Default")
      (node (ref "C15") (pin "1") (pinfunction "1_1") (pintype "passive"))
      (node (ref "C16") (pin "2") (pinfunction "2_2") (pintype "passive"))
      (node (ref "D7") (pin "K") (pinfunction "K_K") (pintype "passive"))
      (node (ref "P2") (pin "1") (pinfunction "1_1") (pintype "passive"))
      (node (ref "P4") (pin "7") (pinfunction "7_7") (pintype "passive"))
      (node (ref "R10") (pin "2") (pinfunction "2_2") (pintype "passive"))
      (node (ref "R9") (pin "2") (pinfunction "2_2") (pintype "passive"))
      (node (ref "U4") (pin "1") (pinfunction "IN_1") (pintype "passive"))
      (node (ref "U4") (pin "3") (pinfunction "EN_3") (pintype "passive"))
    )
    (net (code "84") (name "VCCBAT") (class "Default")
      (node (ref "C4") (pin "2") (pinfunction "2_2") (pintype "passive"))
      (node (ref "C5") (pin "2") (pinfunction "2_2") (pintype "passive"))
      (node (ref "C6") (pin "1") (pinfunction "1_1") (pintype "passive"))
      (node (ref "D5") (pin "A") (pinfunction "A_A") (pintype "passive"))
      (node (ref "Q1") (pin "1") (pinfunction "D_1") (pintype "passive"))
      (node (ref "U2") (pin "2") (pinfunction "VIN_2") (pintype "passive"))
      (node (ref "U2") (pin "3") (pinfunction "EN_3") (pintype "passive"))
    )
    (net (code "85") (name "VCCSreer") (class "Default")
      (node (ref "C2") (pin "1") (pinfunction "1_1") (pintype "passive"))
      (node (ref "C3") (pin "2") (pinfunction "2_2") (pintype "passive"))
      (node (ref "L1") (pin "2") (pinfunction "2_2") (pintype "passive"))
      (node (ref "P5") (pin "2") (pinfunction "2_2") (pintype "passive"))
      (node (ref "R2") (pin "2") (pinfunction "2_2") (pintype "passive"))
      (node (ref "R7") (pin "2") (pinfunction "2_2") (pintype "passive"))
    )
    (net (code "86") (name "unconnected-(P3-Pad7)") (class "Default")
      (node (ref "P3") (pin "7") (pinfunction "7_7") (pintype "passive+no_connect"))
    )
    (net (code "87") (name "unconnected-(P3-Pad8)") (class "Default")
      (node (ref "P3") (pin "8") (pinfunction "8_8") (pintype "passive+no_connect"))
    )
    (net (code "88") (name "unconnected-(P4-Pad2)") (class "Default")
      (node (ref "P4") (pin "2") (pinfunction "2_2") (pintype "passive+no_connect"))
    )
    (net (code "89") (name "unconnected-(S2-B2-Pad3)") (class "Default")
      (node (ref "S2") (pin "3") (pinfunction "B2_3") (pintype "passive"))
    )
    (net (code "90") (name "unconnected-(U4-NC-Pad4)") (class "Default")
      (node (ref "U4") (pin "4") (pinfunction "NC_4") (pintype "passive+no_connect"))
    )
  )
)
